# Prototype.net
KiCad netlist of a schematic drawn in Altium Designer
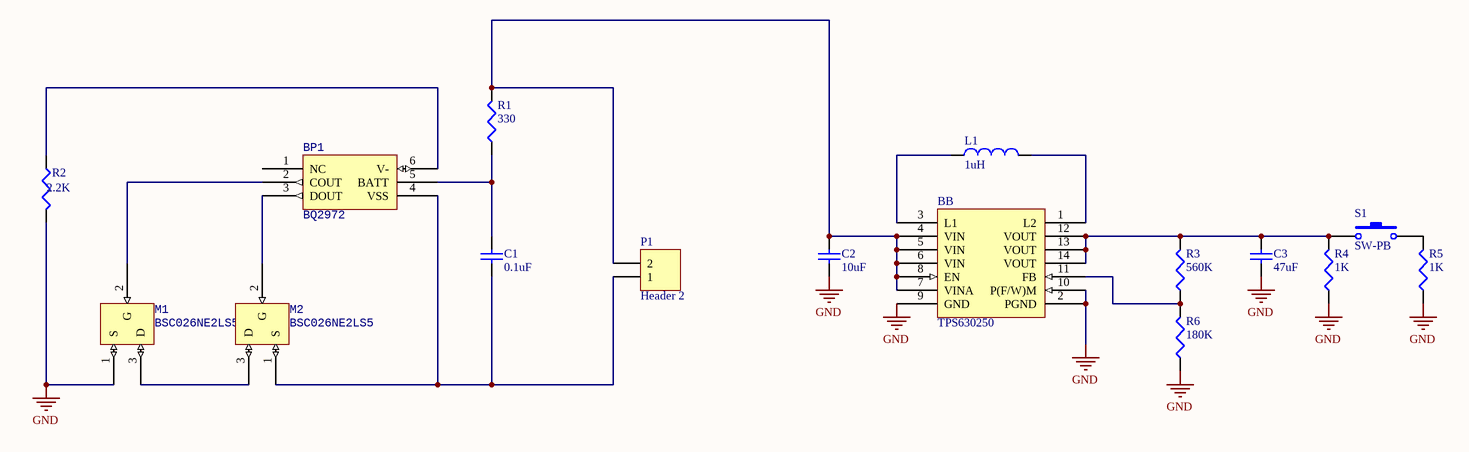
[diagram p0: Prototype.SchDoc]

(export (version "E")
  (design (tool "Eeschema 10.0.6"))
  (components
    (comp (ref "BB")
      (value "TPS630250")
      (footprint "RNC0014A")
      (description "Buck-boost converter")
      (libsource (lib "heron-general") (part "TPS630250"))
    )
    (comp (ref "BP1")
      (value "BQ2972")
      (footprint "SON50P150X150X80-6N")
      (description "Battery protection")
      (libsource (lib "heron-general") (part "BQ2972"))
    )
    (comp (ref "C1")
      (value "0.1uF")
      (footprint "1608[0603]")
      (description "Capacitor")
      (fields (field (name "PUBLISHER") "Altium Limited"))
      (libsource (lib "Miscellaneous Devices") (part "Cap"))
    )
    (comp (ref "C2")
      (value "10uF")
      (footprint "0603")
      (description "Capacitor")
      (fields (field (name "PUBLISHER") "Altium Limited"))
      (libsource (lib "Miscellaneous Devices") (part "Cap"))
    )
    (comp (ref "C3")
      (value "47uF")
      (footprint "0603")
      (description "Capacitor")
      (fields (field (name "PUBLISHER") "Altium Limited"))
      (libsource (lib "Miscellaneous Devices") (part "Cap"))
    )
    (comp (ref "L1")
      (value "1uH")
      (footprint "0402-A")
      (description "Inductor")
      (fields (field (name "PUBLISHER") "Altium Limited"))
      (libsource (lib "Miscellaneous Devices") (part "Inductor"))
    )
    (comp (ref "M1")
      (value "BSC026NE2LS5")
      (footprint "INF-PG-TDSON-8-1_V")
      (description "MOSFET")
      (libsource (lib "heron-general") (part "BSC026NE2LS5"))
    )
    (comp (ref "M2")
      (value "BSC026NE2LS5")
      (footprint "INF-PG-TDSON-8-1_V")
      (description "MOSFET")
      (libsource (lib "") (part "BSC026NE2LS5_1"))
    )
    (comp (ref "P1")
      (value "Header 2")
      (footprint "HDR1X2")
      (description "Header, 2-Pin")
      (fields (field (name "PUBLISHER") "Altium Limited"))
      (libsource (lib "Miscellaneous Connectors") (part "Header 2"))
    )
    (comp (ref "R1")
      (value "330")
      (footprint "J1-0603")
      (description "Resistor")
      (fields (field (name "PUBLISHER") "Altium Limited"))
      (libsource (lib "Miscellaneous Devices") (part "Res3"))
    )
    (comp (ref "R2")
      (value "2.2K")
      (footprint "J1-0603")
      (description "Resistor")
      (fields (field (name "PUBLISHER") "Altium Limited"))
      (libsource (lib "Miscellaneous Devices") (part "Res3"))
    )
    (comp (ref "R3")
      (value "560K")
      (footprint "J1-0603")
      (description "Resistor")
      (fields (field (name "PUBLISHER") "Altium Limited"))
      (libsource (lib "Miscellaneous Devices") (part "Res3"))
    )
    (comp (ref "R4")
      (value "1K")
      (footprint "J1-0603")
      (description "Resistor")
      (fields (field (name "PUBLISHER") "Altium Limited"))
      (libsource (lib "Miscellaneous Devices") (part "Res3"))
    )
    (comp (ref "R5")
      (value "1K")
      (footprint "J1-0603")
      (description "Resistor")
      (fields (field (name "PUBLISHER") "Altium Limited"))
      (libsource (lib "Miscellaneous Devices") (part "Res3"))
    )
    (comp (ref "R6")
      (value "180K")
      (footprint "J1-0603")
      (description "Resistor")
      (fields (field (name "PUBLISHER") "Altium Limited"))
      (libsource (lib "Miscellaneous Devices") (part "Res3"))
    )
    (comp (ref "S1")
      (value "SW-PB")
      (footprint "SPST-2")
      (description "Switch")
      (fields (field (name "PUBLISHER") "Altium Limited"))
      (libsource (lib "Miscellaneous Devices") (part "SW-PB"))
    )
  )
  (nets
    (net (code "1") (name "GND") (class "Default")
      (node (ref "BB") (pin "10") (pinfunction "P(F/W)M_10") (pintype "input"))
      (node (ref "BB") (pin "2") (pinfunction "PGND_2") (pintype "power_in"))
      (node (ref "BB") (pin "9") (pinfunction "GND_9") (pintype "power_in"))
      (node (ref "C2") (pin "1") (pinfunction "1_1") (pintype "passive"))
      (node (ref "C3") (pin "1") (pinfunction "1_1") (pintype "passive"))
      (node (ref "M1") (pin "1") (pinfunction "S_1") (pintype "bidirectional"))
      (node (ref "R2") (pin "2") (pinfunction "2_2") (pintype "passive"))
      (node (ref "R4") (pin "1") (pinfunction "1_1") (pintype "passive"))
      (node (ref "R5") (pin "1") (pinfunction "1_1") (pintype "passive"))
      (node (ref "R6") (pin "1") (pinfunction "1_1") (pintype "passive"))
    )
    (net (code "2") (name "Net-(BB-EN)") (class "Default")
      (node (ref "BB") (pin "4") (pinfunction "VIN_4") (pintype "power_in"))
      (node (ref "BB") (pin "5") (pinfunction "VIN_5") (pintype "power_in"))
      (node (ref "BB") (pin "6") (pinfunction "VIN_6") (pintype "power_in"))
      (node (ref "BB") (pin "7") (pinfunction "VINA_7") (pintype "power_in"))
      (node (ref "BB") (pin "8") (pinfunction "EN_8") (pintype "input"))
      (node (ref "C2") (pin "2") (pinfunction "2_2") (pintype "passive"))
      (node (ref "P1") (pin "2") (pinfunction "2_2") (pintype "passive"))
      (node (ref "R1") (pin "2") (pinfunction "2_2") (pintype "passive"))
    )
    (net (code "3") (name "Net-(BB-FB)") (class "Default")
      (node (ref "BB") (pin "11") (pinfunction "FB_11") (pintype "input"))
      (node (ref "R3") (pin "1") (pinfunction "1_1") (pintype "passive"))
      (node (ref "R6") (pin "2") (pinfunction "2_2") (pintype "passive"))
    )
    (net (code "4") (name "Net-(BB-L1)") (class "Default")
      (node (ref "BB") (pin "3") (pinfunction "L1_3") (pintype "power_in"))
      (node (ref "L1") (pin "1") (pinfunction "1_1") (pintype "passive"))
    )
    (net (code "5") (name "Net-(BB-L2)") (class "Default")
      (node (ref "BB") (pin "1") (pinfunction "L2_1") (pintype "power_in"))
      (node (ref "L1") (pin "2") (pinfunction "2_2") (pintype "passive"))
    )
    (net (code "6") (name "Net-(BB-VOUT-Pad12)") (class "Default")
      (node (ref "BB") (pin "12") (pinfunction "VOUT_12") (pintype "passive"))
      (node (ref "BB") (pin "13") (pinfunction "VOUT_13") (pintype "passive"))
      (node (ref "BB") (pin "14") (pinfunction "VOUT_14") (pintype "passive"))
      (node (ref "C3") (pin "2") (pinfunction "2_2") (pintype "passive"))
      (node (ref "R3") (pin "2") (pinfunction "2_2") (pintype "passive"))
      (node (ref "R4") (pin "2") (pinfunction "2_2") (pintype "passive"))
      (node (ref "S1") (pin "1") (pinfunction "1_1") (pintype "passive"))
    )
    (net (code "7") (name "Net-(BP1-BATT)") (class "Default")
      (node (ref "BP1") (pin "5") (pinfunction "BATT_5") (pintype "power_in"))
      (node (ref "C1") (pin "2") (pinfunction "2_2") (pintype "passive"))
      (node (ref "R1") (pin "1") (pinfunction "1_1") (pintype "passive"))
    )
    (net (code "8") (name "Net-(BP1-COUT)") (class "Default")
      (node (ref "BP1") (pin "2") (pinfunction "COUT_2") (pintype "output"))
      (node (ref "M1") (pin "2") (pinfunction "G_2") (pintype "input"))
    )
    (net (code "9") (name "Net-(BP1-DOUT)") (class "Default")
      (node (ref "BP1") (pin "3") (pinfunction "DOUT_3") (pintype "output"))
      (node (ref "M2") (pin "2") (pinfunction "G_2") (pintype "input"))
    )
    (net (code "10") (name "Net-(BP1-V-)") (class "Default")
      (node (ref "BP1") (pin "6") (pinfunction "V-_6") (pintype "bidirectional"))
      (node (ref "R2") (pin "1") (pinfunction "1_1") (pintype "passive"))
    )
    (net (code "11") (name "Net-(BP1-VSS)") (class "Default")
      (node (ref "BP1") (pin "4") (pinfunction "VSS_4") (pintype "power_in"))
      (node (ref "C1") (pin "1") (pinfunction "1_1") (pintype "passive"))
      (node (ref "M2") (pin "1") (pinfunction "S_1") (pintype "bidirectional"))
      (node (ref "P1") (pin "1") (pinfunction "1_1") (pintype "passive"))
    )
    (net (code "12") (name "Net-(M1-D)") (class "Default")
      (node (ref "M1") (pin "3") (pinfunction "D_3") (pintype "bidirectional"))
      (node (ref "M2") (pin "3") (pinfunction "D_3") (pintype "bidirectional"))
    )
    (net (code "13") (name "Net-(R5-Pad2)") (class "Default")
      (node (ref "R5") (pin "2") (pinfunction "2_2") (pintype "passive"))
      (node (ref "S1") (pin "2") (pinfunction "2_2") (pintype "passive"))
    )
    (net (code "14") (name "unconnected-(BP1-NC-Pad1)") (class "Default")
      (node (ref "BP1") (pin "1") (pinfunction "NC_1") (pintype "passive"))
    )
  )
)
